# schematic.net
KiCad netlist of a schematic drawn in Altium Designer
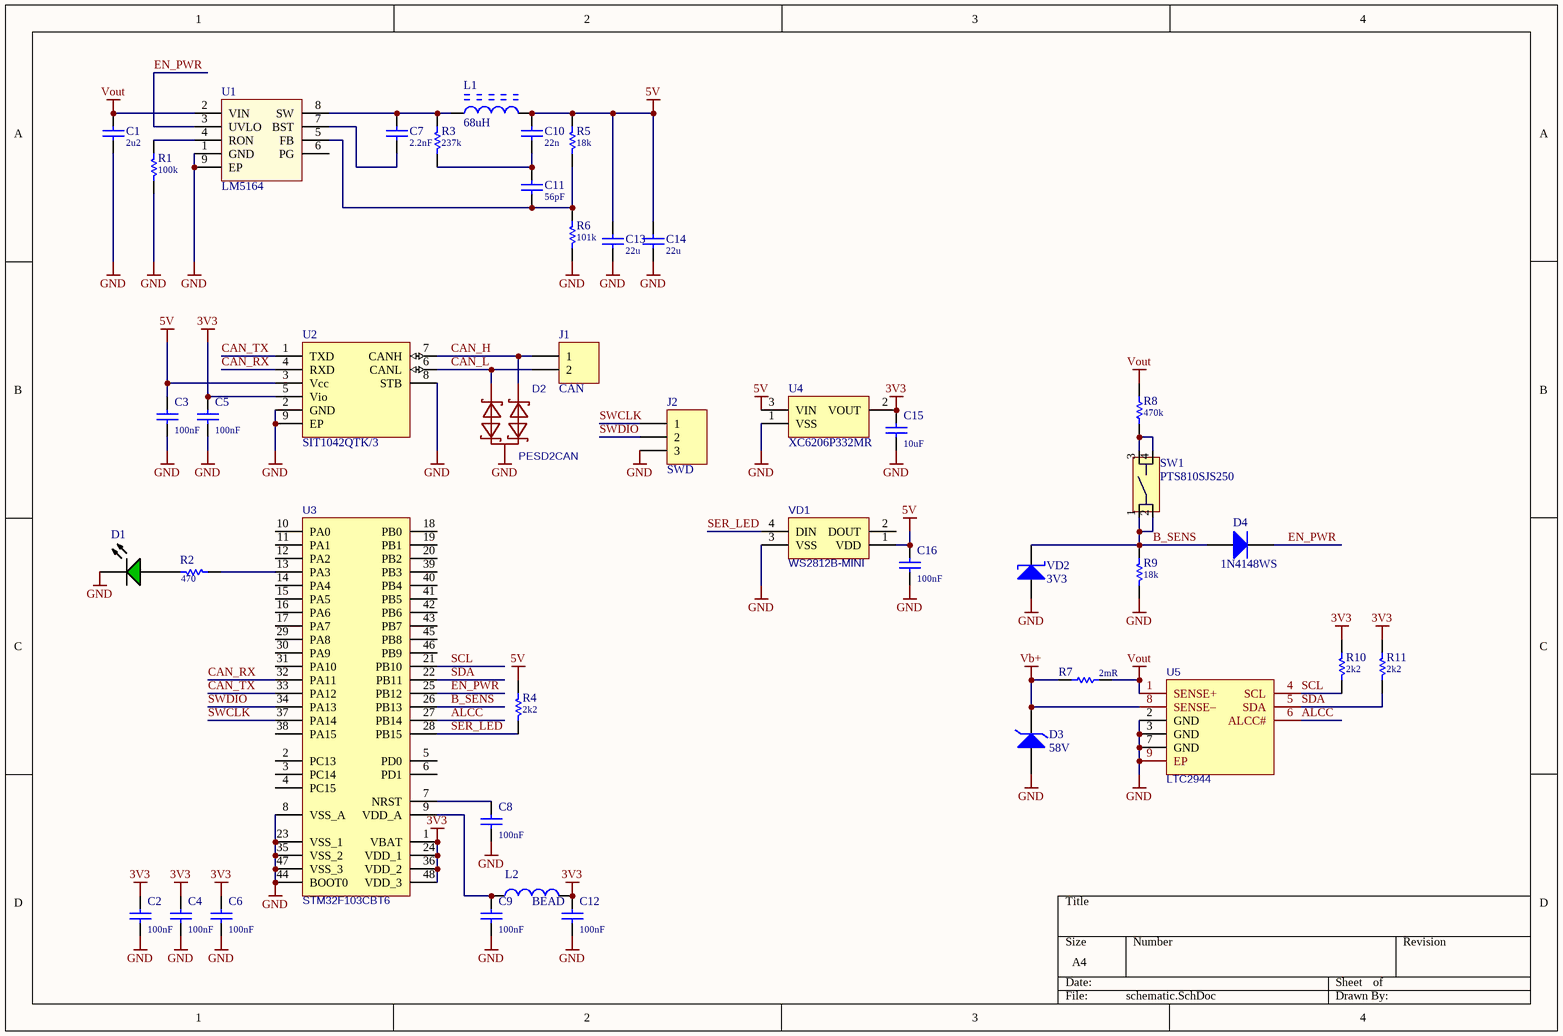
[diagram p0: schematic.SchDoc]

(export (version "E")
  (design (tool "Eeschema 10.0.6"))
  (components
    (comp (ref "C1")
      (value "2u2")
      (footprint "C1210")
      (description "2.2uF 100V 1210")
      (libsource (lib "Miscellaneous Devices") (part "CAP"))
    )
    (comp (ref "C2")
      (value "100nF")
      (footprint "C0402")
      (description "100nF 50V 0402")
      (libsource (lib "Miscellaneous Devices") (part "CAP"))
    )
    (comp (ref "C3")
      (value "100nF")
      (footprint "C0402")
      (description "100nF 50V 0402")
      (libsource (lib "Miscellaneous Devices") (part "CAP"))
    )
    (comp (ref "C4")
      (value "100nF")
      (footprint "C0402")
      (description "100nF 50V 0402")
      (libsource (lib "Miscellaneous Devices") (part "CAP"))
    )
    (comp (ref "C5")
      (value "100nF")
      (footprint "C0402")
      (description "100nF 50V 0402")
      (libsource (lib "Miscellaneous Devices") (part "CAP"))
    )
    (comp (ref "C6")
      (value "100nF")
      (footprint "C0402")
      (description "100nF 50V 0402")
      (libsource (lib "Miscellaneous Devices") (part "CAP"))
    )
    (comp (ref "C7")
      (value "2.2nF")
      (footprint "C0603")
      (description "2.2nF 50V 0603")
      (libsource (lib "Miscellaneous Devices") (part "CAP"))
    )
    (comp (ref "C8")
      (value "100nF")
      (footprint "C0402")
      (description "100nF 50V 0402")
      (libsource (lib "Miscellaneous Devices") (part "CAP"))
    )
    (comp (ref "C9")
      (value "100nF")
      (footprint "C0402")
      (description "100nF 50V 0402")
      (libsource (lib "Miscellaneous Devices") (part "CAP"))
    )
    (comp (ref "C10")
      (value "22n")
      (footprint "C0603")
      (description "2.2nF 0603")
      (libsource (lib "Miscellaneous Devices") (part "CAP"))
    )
    (comp (ref "C11")
      (value "56pF")
      (footprint "C0603")
      (description "56pF 0603")
      (libsource (lib "Miscellaneous Devices") (part "CAP"))
    )
    (comp (ref "C12")
      (value "100nF")
      (footprint "C0402")
      (description "100nF 50V 0402")
      (libsource (lib "Miscellaneous Devices") (part "CAP"))
    )
    (comp (ref "C13")
      (value "22u")
      (footprint "C1210")
      (description "22u 35V 1210")
      (libsource (lib "Miscellaneous Devices") (part "CAP"))
    )
    (comp (ref "C14")
      (value "22u")
      (footprint "C1210")
      (description "22u 35V 1210")
      (libsource (lib "Miscellaneous Devices") (part "CAP"))
    )
    (comp (ref "C15")
      (value "10uF")
      (footprint "C0603")
      (description "10uf 50V 1206")
      (libsource (lib "Miscellaneous Devices") (part "CAP"))
    )
    (comp (ref "C16")
      (value "100nF")
      (footprint "C0402")
      (description "100nF 50V 0402")
      (fields (field (name "LCSC PART NUMBER") "C131394"))
      (libsource (lib "Miscellaneous Devices") (part "CAP"))
    )
    (comp (ref "D1")
      (value "GRN")
      (footprint "LED-0603-GRN")
      (description "LED 0603 GRN")
      (libsource (lib "Miscellaneous Devices") (part "LED-0603-GREEN"))
    )
    (comp (ref "D2")
      (value "PESD2CAN")
      (footprint "SOT-23")
      (fields (field (name "LCSC PART NUMBER") "C5261081"))
      (libsource (lib "Miscellaneous Devices") (part "CDSOT23-SM712"))
    )
    (comp (ref "D3")
      (value "58V")
      (footprint "SMA")
      (description "SMAJ58A")
      (fields (field (name "LCSC PART NUMBER") "C693617"))
      (libsource (lib "Miscellaneous Devices") (part "NCP51460SN33T1G"))
    )
    (comp (ref "D4")
      (value "1N4148WS")
      (footprint "SOD-323")
      (libsource (lib "Miscellaneous Devices") (part "US1M-13-F"))
    )
    (comp (ref "J1") (value "CAN") (footprint "HDR-1X2") (libsource (lib "Schlib1") (part "Header 2")))
    (comp (ref "J2")
      (value "SWD")
      (footprint "HDR-1x3-P1.25")
      (libsource (lib "Miscellaneous Devices") (part "Header 3"))
    )
    (comp (ref "L1")
      (value "68uH")
      (footprint "L0605-POWER")
      (description "PSPMAA0605H-680M-IGF")
      (libsource (lib "Miscellaneous Devices") (part "SRN3015-100M"))
    )
    (comp (ref "L2")
      (value "BEAD")
      (footprint "L0402")
      (description "BEAD 0402")
      (libsource (lib "Miscellaneous Devices") (part "BLM18AG601SN1D"))
    )
    (comp (ref "R1")
      (value "100k")
      (footprint "R0603")
      (description "100k 0603")
      (libsource (lib "Miscellaneous Devices") (part "RES"))
    )
    (comp (ref "R2") (value "470") (footprint "R0402") (libsource (lib "Miscellaneous Devices") (part "RES")))
    (comp (ref "R3")
      (value "237k")
      (footprint "R0603")
      (description "237k 0603")
      (libsource (lib "Miscellaneous Devices") (part "RES"))
    )
    (comp (ref "R4") (value "2k2") (footprint "R0402") (libsource (lib "Miscellaneous Devices") (part "RES")))
    (comp (ref "R5")
      (value "18k")
      (footprint "R0603")
      (description "18k 0603")
      (libsource (lib "Miscellaneous Devices") (part "RES"))
    )
    (comp (ref "R6")
      (value "101k")
      (footprint "R0603")
      (description "101k 0603")
      (libsource (lib "Miscellaneous Devices") (part "RES"))
    )
    (comp (ref "R7")
      (value "2mR")
      (footprint "R2512-WIDE")
      (description "2mR shunt 2512")
      (fields (field (name "LCSC PART NUMBER") "C728320"))
      (libsource (lib "Miscellaneous Devices") (part "RES"))
    )
    (comp (ref "R8")
      (value "470k")
      (footprint "R1206")
      (description "470k 1206")
      (libsource (lib "Miscellaneous Devices") (part "RES"))
    )
    (comp (ref "R9")
      (value "18k")
      (footprint "R0603")
      (description "18k 0603")
      (libsource (lib "Miscellaneous Devices") (part "RES"))
    )
    (comp (ref "R10")
      (value "2k2")
      (footprint "R0402")
      (libsource (lib "Miscellaneous Devices") (part "RES"))
    )
    (comp (ref "R11")
      (value "2k2")
      (footprint "R0402")
      (libsource (lib "Miscellaneous Devices") (part "RES"))
    )
    (comp (ref "SW1")
      (value "PTS810SJS250")
      (footprint "BTN_PTS810")
      (libsource (lib "Miscellaneous Devices") (part "Component_1"))
    )
    (comp (ref "U1") (value "LM5164") (footprint "PowerSOIC-8") (libsource (lib "Schlib2") (part "LM5164")))
    (comp (ref "U2")
      (value "SIT1042QTK/3")
      (footprint "DFN8_3X3_P065")
      (description "IC INTERFACE CAN")
      (libsource (lib "Miscellaneous Devices") (part "LTC2875"))
    )
    (comp (ref "U3")
      (value "STM32F103CBT6")
      (footprint "LQFP-48")
      (libsource (lib "Schlib1") (part "STM32F103CBT6"))
    )
    (comp (ref "U4")
      (value "XC6206P332MR")
      (footprint "SOT-23")
      (libsource (lib "Schlib1") (part "Component_4_1"))
    )
    (comp (ref "U5")
      (value "LTC2944")
      (footprint "DFN8_3X3_P05")
      (description "LTC2944IDD#TRPBF")
      (fields (field (name "LCSC PART NUMBER") "C683673"))
      (libsource (lib "Schlib1") (part "LTC2944IDD#TRPBF"))
    )
    (comp (ref "VD1")
      (value "WS2812B-MINI")
      (footprint "LED-SMD_4P-L3.5-W3.5-TL_WS2812B")
      (fields (field (name "LCSC PART NUMBER") "C527089"))
      (libsource (lib "Schlib1") (part "WS2812B-MINI"))
    )
    (comp (ref "VD2")
      (value "3V3")
      (footprint "SOD-123")
      (description "Zener 3.3V")
      (libsource (lib "Schlib1") (part "ZENER"))
    )
  )
  (nets
    (net (code "1") (name "/ALCC") (class "Default")
      (node (ref "U3") (pin "27") (pinfunction "PB14_27") (pintype "passive"))
      (node (ref "U5") (pin "6") (pinfunction "ALCC#_6") (pintype "passive"))
    )
    (net (code "2") (name "/B_SENS") (class "Default")
      (node (ref "D4") (pin "1") (pinfunction "A_1") (pintype "passive"))
      (node (ref "R9") (pin "2") (pinfunction "2_2") (pintype "passive"))
      (node (ref "SW1") (pin "1") (pinfunction "1_1") (pintype "passive"))
      (node (ref "SW1") (pin "2") (pinfunction "2_2") (pintype "passive"))
      (node (ref "U3") (pin "26") (pinfunction "PB13_26") (pintype "passive"))
      (node (ref "VD2") (pin "2") (pinfunction "C_2") (pintype "passive"))
    )
    (net (code "3") (name "/CAN_H") (class "Default")
      (node (ref "D2") (pin "2") (pinfunction "2_2") (pintype "passive"))
      (node (ref "J1") (pin "1") (pinfunction "1_1") (pintype "passive"))
      (node (ref "U2") (pin "7") (pinfunction "CANH_7") (pintype "bidirectional"))
    )
    (net (code "4") (name "/CAN_L") (class "Default")
      (node (ref "D2") (pin "1") (pinfunction "1_1") (pintype "passive"))
      (node (ref "J1") (pin "2") (pinfunction "2_2") (pintype "passive"))
      (node (ref "U2") (pin "6") (pinfunction "CANL_6") (pintype "bidirectional"))
    )
    (net (code "5") (name "/CAN_RX") (class "Default")
      (node (ref "U2") (pin "4") (pinfunction "RXD_4") (pintype "passive"))
      (node (ref "U3") (pin "32") (pinfunction "PA11_32") (pintype "passive"))
    )
    (net (code "6") (name "/CAN_TX") (class "Default")
      (node (ref "U2") (pin "1") (pinfunction "TXD_1") (pintype "passive"))
      (node (ref "U3") (pin "33") (pinfunction "PA12_33") (pintype "passive"))
    )
    (net (code "7") (name "/EN_PWR") (class "Default")
      (node (ref "D4") (pin "2") (pinfunction "K_2") (pintype "passive"))
      (node (ref "U1") (pin "3") (pinfunction "UVLO_3") (pintype "passive"))
      (node (ref "U3") (pin "25") (pinfunction "PB12_25") (pintype "passive"))
    )
    (net (code "8") (name "/SCL") (class "Default")
      (node (ref "R10") (pin "1") (pinfunction "1_1") (pintype "passive"))
      (node (ref "U3") (pin "21") (pinfunction "PB10_21") (pintype "passive"))
      (node (ref "U5") (pin "4") (pinfunction "SCL_4") (pintype "passive"))
    )
    (net (code "9") (name "/SDA") (class "Default")
      (node (ref "R11") (pin "1") (pinfunction "1_1") (pintype "passive"))
      (node (ref "U3") (pin "22") (pinfunction "PB11_22") (pintype "passive"))
      (node (ref "U5") (pin "5") (pinfunction "SDA_5") (pintype "passive"))
    )
    (net (code "10") (name "/SER_LED") (class "Default")
      (node (ref "R4") (pin "1") (pinfunction "1_1") (pintype "passive"))
      (node (ref "U3") (pin "28") (pinfunction "PB15_28") (pintype "passive"))
      (node (ref "VD1") (pin "4") (pinfunction "DIN_4") (pintype "passive"))
    )
    (net (code "11") (name "/SWCLK") (class "Default")
      (node (ref "J2") (pin "1") (pinfunction "1_1") (pintype "passive"))
      (node (ref "U3") (pin "37") (pinfunction "PA14_37") (pintype "passive"))
    )
    (net (code "12") (name "/SWDIO") (class "Default")
      (node (ref "J2") (pin "2") (pinfunction "2_2") (pintype "passive"))
      (node (ref "U3") (pin "34") (pinfunction "PA13_34") (pintype "passive"))
    )
    (net (code "13") (name "3V3") (class "Default")
      (node (ref "C12") (pin "2") (pinfunction "2_2") (pintype "passive"))
      (node (ref "C15") (pin "2") (pinfunction "2_2") (pintype "passive"))
      (node (ref "C2") (pin "2") (pinfunction "2_2") (pintype "passive"))
      (node (ref "C4") (pin "2") (pinfunction "2_2") (pintype "passive"))
      (node (ref "C5") (pin "2") (pinfunction "2_2") (pintype "passive"))
      (node (ref "C6") (pin "2") (pinfunction "2_2") (pintype "passive"))
      (node (ref "L2") (pin "1") (pinfunction "1_1") (pintype "passive"))
      (node (ref "R10") (pin "2") (pinfunction "2_2") (pintype "passive"))
      (node (ref "R11") (pin "2") (pinfunction "2_2") (pintype "passive"))
      (node (ref "U2") (pin "5") (pinfunction "Vio_5") (pintype "passive"))
      (node (ref "U3") (pin "1") (pinfunction "VBAT_1") (pintype "passive"))
      (node (ref "U3") (pin "24") (pinfunction "VDD_1_24") (pintype "passive"))
      (node (ref "U3") (pin "36") (pinfunction "VDD_2_36") (pintype "passive"))
      (node (ref "U3") (pin "48") (pinfunction "VDD_3_48") (pintype "passive"))
      (node (ref "U4") (pin "2") (pinfunction "VOUT_2") (pintype "passive"))
    )
    (net (code "14") (name "5V") (class "Default")
      (node (ref "C10") (pin "2") (pinfunction "2_2") (pintype "passive"))
      (node (ref "C13") (pin "2") (pinfunction "2_2") (pintype "passive"))
      (node (ref "C14") (pin "2") (pinfunction "2_2") (pintype "passive"))
      (node (ref "C16") (pin "2") (pinfunction "2_2") (pintype "passive"))
      (node (ref "C3") (pin "2") (pinfunction "2_2") (pintype "passive"))
      (node (ref "L1") (pin "2") (pinfunction "2_2") (pintype "passive"))
      (node (ref "R4") (pin "2") (pinfunction "2_2") (pintype "passive"))
      (node (ref "R5") (pin "1") (pinfunction "1_1") (pintype "passive"))
      (node (ref "U2") (pin "3") (pinfunction "Vcc_3") (pintype "passive"))
      (node (ref "U4") (pin "3") (pinfunction "VIN_3") (pintype "passive"))
      (node (ref "VD1") (pin "1") (pinfunction "VDD_1") (pintype "passive"))
    )
    (net (code "15") (name "GND") (class "Default")
      (node (ref "C1") (pin "1") (pinfunction "1_1") (pintype "passive"))
      (node (ref "C12") (pin "1") (pinfunction "1_1") (pintype "passive"))
      (node (ref "C13") (pin "1") (pinfunction "1_1") (pintype "passive"))
      (node (ref "C14") (pin "1") (pinfunction "1_1") (pintype "passive"))
      (node (ref "C15") (pin "1") (pinfunction "1_1") (pintype "passive"))
      (node (ref "C16") (pin "1") (pinfunction "1_1") (pintype "passive"))
      (node (ref "C2") (pin "1") (pinfunction "1_1") (pintype "passive"))
      (node (ref "C3") (pin "1") (pinfunction "1_1") (pintype "passive"))
      (node (ref "C4") (pin "1") (pinfunction "1_1") (pintype "passive"))
      (node (ref "C5") (pin "1") (pinfunction "1_1") (pintype "passive"))
      (node (ref "C6") (pin "1") (pinfunction "1_1") (pintype "passive"))
      (node (ref "C8") (pin "1") (pinfunction "1_1") (pintype "passive"))
      (node (ref "C9") (pin "1") (pinfunction "1_1") (pintype "passive"))
      (node (ref "D1") (pin "2") (pinfunction "K_2") (pintype "passive"))
      (node (ref "D2") (pin "3") (pinfunction "3_3") (pintype "passive"))
      (node (ref "D3") (pin "1") (pinfunction "-_1") (pintype "passive"))
      (node (ref "J2") (pin "3") (pinfunction "3_3") (pintype "passive"))
      (node (ref "R1") (pin "2") (pinfunction "2_2") (pintype "passive"))
      (node (ref "R6") (pin "2") (pinfunction "2_2") (pintype "passive"))
      (node (ref "R9") (pin "1") (pinfunction "1_1") (pintype "passive"))
      (node (ref "U1") (pin "1") (pinfunction "GND_1") (pintype "power_in"))
      (node (ref "U1") (pin "9") (pinfunction "EP_9") (pintype "passive"))
      (node (ref "U2") (pin "2") (pinfunction "GND_2") (pintype "passive"))
      (node (ref "U2") (pin "8") (pinfunction "STB_8") (pintype "passive"))
      (node (ref "U2") (pin "9") (pinfunction "EP_9") (pintype "passive"))
      (node (ref "U3") (pin "23") (pinfunction "VSS_1_23") (pintype "passive"))
      (node (ref "U3") (pin "35") (pinfunction "VSS_2_35") (pintype "passive"))
      (node (ref "U3") (pin "44") (pinfunction "BOOT0_44") (pintype "passive"))
      (node (ref "U3") (pin "47") (pinfunction "VSS_3_47") (pintype "passive"))
      (node (ref "U3") (pin "8") (pinfunction "VSS_A_8") (pintype "passive"))
      (node (ref "U4") (pin "1") (pinfunction "VSS_1") (pintype "passive"))
      (node (ref "U5") (pin "2") (pinfunction "GND_2") (pintype "passive"))
      (node (ref "U5") (pin "3") (pinfunction "GND_3") (pintype "passive"))
      (node (ref "U5") (pin "7") (pinfunction "GND_7") (pintype "passive"))
      (node (ref "U5") (pin "9") (pinfunction "EP_9") (pintype "passive"))
      (node (ref "VD1") (pin "3") (pinfunction "VSS_3") (pintype "passive"))
      (node (ref "VD2") (pin "1") (pinfunction "A_1") (pintype "passive"))
    )
    (net (code "16") (name "Net-(C10-Pad1)") (class "Default")
      (node (ref "C10") (pin "1") (pinfunction "1_1") (pintype "passive"))
      (node (ref "C11") (pin "2") (pinfunction "2_2") (pintype "passive"))
      (node (ref "R3") (pin "2") (pinfunction "2_2") (pintype "passive"))
    )
    (net (code "17") (name "Net-(D1-A)") (class "Default")
      (node (ref "D1") (pin "1") (pinfunction "A_1") (pintype "passive"))
      (node (ref "R2") (pin "1") (pinfunction "1_1") (pintype "passive"))
    )
    (net (code "18") (name "Net-(R8-Pad2)") (class "Default")
      (node (ref "R8") (pin "2") (pinfunction "2_2") (pintype "passive"))
      (node (ref "SW1") (pin "3") (pinfunction "3_3") (pintype "passive"))
      (node (ref "SW1") (pin "4") (pinfunction "4_4") (pintype "passive"))
    )
    (net (code "19") (name "Net-(U1-BST)") (class "Default")
      (node (ref "C7") (pin "1") (pinfunction "1_1") (pintype "passive"))
      (node (ref "U1") (pin "7") (pinfunction "BST_7") (pintype "passive"))
    )
    (net (code "20") (name "Net-(U1-FB)") (class "Default")
      (node (ref "C11") (pin "1") (pinfunction "1_1") (pintype "passive"))
      (node (ref "R5") (pin "2") (pinfunction "2_2") (pintype "passive"))
      (node (ref "R6") (pin "1") (pinfunction "1_1") (pintype "passive"))
      (node (ref "U1") (pin "5") (pinfunction "FB_5") (pintype "power_in"))
    )
    (net (code "21") (name "Net-(U1-RON)") (class "Default")
      (node (ref "R1") (pin "1") (pinfunction "1_1") (pintype "passive"))
      (node (ref "U1") (pin "4") (pinfunction "RON_4") (pintype "power_in"))
    )
    (net (code "22") (name "Net-(U1-SW)") (class "Default")
      (node (ref "C7") (pin "2") (pinfunction "2_2") (pintype "passive"))
      (node (ref "L1") (pin "1") (pinfunction "1_1") (pintype "passive"))
      (node (ref "R3") (pin "1") (pinfunction "1_1") (pintype "passive"))
      (node (ref "U1") (pin "8") (pinfunction "SW_8") (pintype "power_in"))
    )
    (net (code "23") (name "Net-(U3-NRST)") (class "Default")
      (node (ref "C8") (pin "2") (pinfunction "2_2") (pintype "passive"))
      (node (ref "U3") (pin "7") (pinfunction "NRST_7") (pintype "passive"))
    )
    (net (code "24") (name "Net-(U3-PA3)") (class "Default")
      (node (ref "R2") (pin "2") (pinfunction "2_2") (pintype "passive"))
      (node (ref "U3") (pin "13") (pinfunction "PA3_13") (pintype "passive"))
    )
    (net (code "25") (name "Net-(U3-VDD_A)") (class "Default")
      (node (ref "C9") (pin "2") (pinfunction "2_2") (pintype "passive"))
      (node (ref "L2") (pin "2") (pinfunction "2_2") (pintype "passive"))
      (node (ref "U3") (pin "9") (pinfunction "VDD_A_9") (pintype "passive"))
    )
    (net (code "26") (name "Vb+") (class "Default")
      (node (ref "D3") (pin "2") (pinfunction "+_2") (pintype "passive"))
      (node (ref "R7") (pin "1") (pinfunction "1_1") (pintype "passive"))
      (node (ref "U5") (pin "8") (pinfunction "SENSE–_8") (pintype "passive"))
    )
    (net (code "27") (name "Vout") (class "Default")
      (node (ref "C1") (pin "2") (pinfunction "2_2") (pintype "passive"))
      (node (ref "R7") (pin "2") (pinfunction "2_2") (pintype "passive"))
      (node (ref "R8") (pin "1") (pinfunction "1_1") (pintype "passive"))
      (node (ref "U1") (pin "2") (pinfunction "VIN_2") (pintype "power_in"))
      (node (ref "U5") (pin "1") (pinfunction "SENSE+_1") (pintype "passive"))
    )
    (net (code "28") (name "unconnected-(U1-PG-Pad6)") (class "Default")
      (node (ref "U1") (pin "6") (pinfunction "PG_6") (pintype "open_collector"))
    )
    (net (code "29") (name "unconnected-(U3-PA0-Pad10)") (class "Default")
      (node (ref "U3") (pin "10") (pinfunction "PA0_10") (pintype "passive"))
    )
    (net (code "30") (name "unconnected-(U3-PA1-Pad11)") (class "Default")
      (node (ref "U3") (pin "11") (pinfunction "PA1_11") (pintype "passive"))
    )
    (net (code "31") (name "unconnected-(U3-PA2-Pad12)") (class "Default")
      (node (ref "U3") (pin "12") (pinfunction "PA2_12") (pintype "passive"))
    )
    (net (code "32") (name "unconnected-(U3-PA4-Pad14)") (class "Default")
      (node (ref "U3") (pin "14") (pinfunction "PA4_14") (pintype "passive"))
    )
    (net (code "33") (name "unconnected-(U3-PA5-Pad15)") (class "Default")
      (node (ref "U3") (pin "15") (pinfunction "PA5_15") (pintype "passive"))
    )
    (net (code "34") (name "unconnected-(U3-PA6-Pad16)") (class "Default")
      (node (ref "U3") (pin "16") (pinfunction "PA6_16") (pintype "passive"))
    )
    (net (code "35") (name "unconnected-(U3-PA7-Pad17)") (class "Default")
      (node (ref "U3") (pin "17") (pinfunction "PA7_17") (pintype "passive"))
    )
    (net (code "36") (name "unconnected-(U3-PA8-Pad29)") (class "Default")
      (node (ref "U3") (pin "29") (pinfunction "PA8_29") (pintype "passive"))
    )
    (net (code "37") (name "unconnected-(U3-PA9-Pad30)") (class "Default")
      (node (ref "U3") (pin "30") (pinfunction "PA9_30") (pintype "passive"))
    )
    (net (code "38") (name "unconnected-(U3-PA10-Pad31)") (class "Default")
      (node (ref "U3") (pin "31") (pinfunction "PA10_31") (pintype "passive"))
    )
    (net (code "39") (name "unconnected-(U3-PA15-Pad38)") (class "Default")
      (node (ref "U3") (pin "38") (pinfunction "PA15_38") (pintype "passive"))
    )
    (net (code "40") (name "unconnected-(U3-PB0-Pad18)") (class "Default")
      (node (ref "U3") (pin "18") (pinfunction "PB0_18") (pintype "passive"))
    )
    (net (code "41") (name "unconnected-(U3-PB1-Pad19)") (class "Default")
      (node (ref "U3") (pin "19") (pinfunction "PB1_19") (pintype "passive"))
    )
    (net (code "42") (name "unconnected-(U3-PB2-Pad20)") (class "Default")
      (node (ref "U3") (pin "20") (pinfunction "PB2_20") (pintype "passive"))
    )
    (net (code "43") (name "unconnected-(U3-PB3-Pad39)") (class "Default")
      (node (ref "U3") (pin "39") (pinfunction "PB3_39") (pintype "passive"))
    )
    (net (code "44") (name "unconnected-(U3-PB4-Pad40)") (class "Default")
      (node (ref "U3") (pin "40") (pinfunction "PB4_40") (pintype "passive"))
    )
    (net (code "45") (name "unconnected-(U3-PB5-Pad41)") (class "Default")
      (node (ref "U3") (pin "41") (pinfunction "PB5_41") (pintype "passive"))
    )
    (net (code "46") (name "unconnected-(U3-PB6-Pad42)") (class "Default")
      (node (ref "U3") (pin "42") (pinfunction "PB6_42") (pintype "passive"))
    )
    (net (code "47") (name "unconnected-(U3-PB7-Pad43)") (class "Default")
      (node (ref "U3") (pin "43") (pinfunction "PB7_43") (pintype "passive"))
    )
    (net (code "48") (name "unconnected-(U3-PB8-Pad45)") (class "Default")
      (node (ref "U3") (pin "45") (pinfunction "PB8_45") (pintype "passive"))
    )
    (net (code "49") (name "unconnected-(U3-PB9-Pad46)") (class "Default")
      (node (ref "U3") (pin "46") (pinfunction "PB9_46") (pintype "passive"))
    )
    (net (code "50") (name "unconnected-(U3-PC13-Pad2)") (class "Default")
      (node (ref "U3") (pin "2") (pinfunction "PC13_2") (pintype "passive"))
    )
    (net (code "51") (name "unconnected-(U3-PC14-Pad3)") (class "Default")
      (node (ref "U3") (pin "3") (pinfunction "PC14_3") (pintype "passive"))
    )
    (net (code "52") (name "unconnected-(U3-PC15-Pad4)") (class "Default")
      (node (ref "U3") (pin "4") (pinfunction "PC15_4") (pintype "passive"))
    )
    (net (code "53") (name "unconnected-(U3-PD0-Pad5)") (class "Default")
      (node (ref "U3") (pin "5") (pinfunction "PD0_5") (pintype "passive"))
    )
    (net (code "54") (name "unconnected-(U3-PD1-Pad6)") (class "Default")
      (node (ref "U3") (pin "6") (pinfunction "PD1_6") (pintype "passive"))
    )
    (net (code "55") (name "unconnected-(VD1-DOUT-Pad2)") (class "Default")
      (node (ref "VD1") (pin "2") (pinfunction "DOUT_2") (pintype "passive"))
    )
  )
)
